# LiPo-USB-Charger-v10.net
KiCad netlist of a schematic drawn in EAGLE
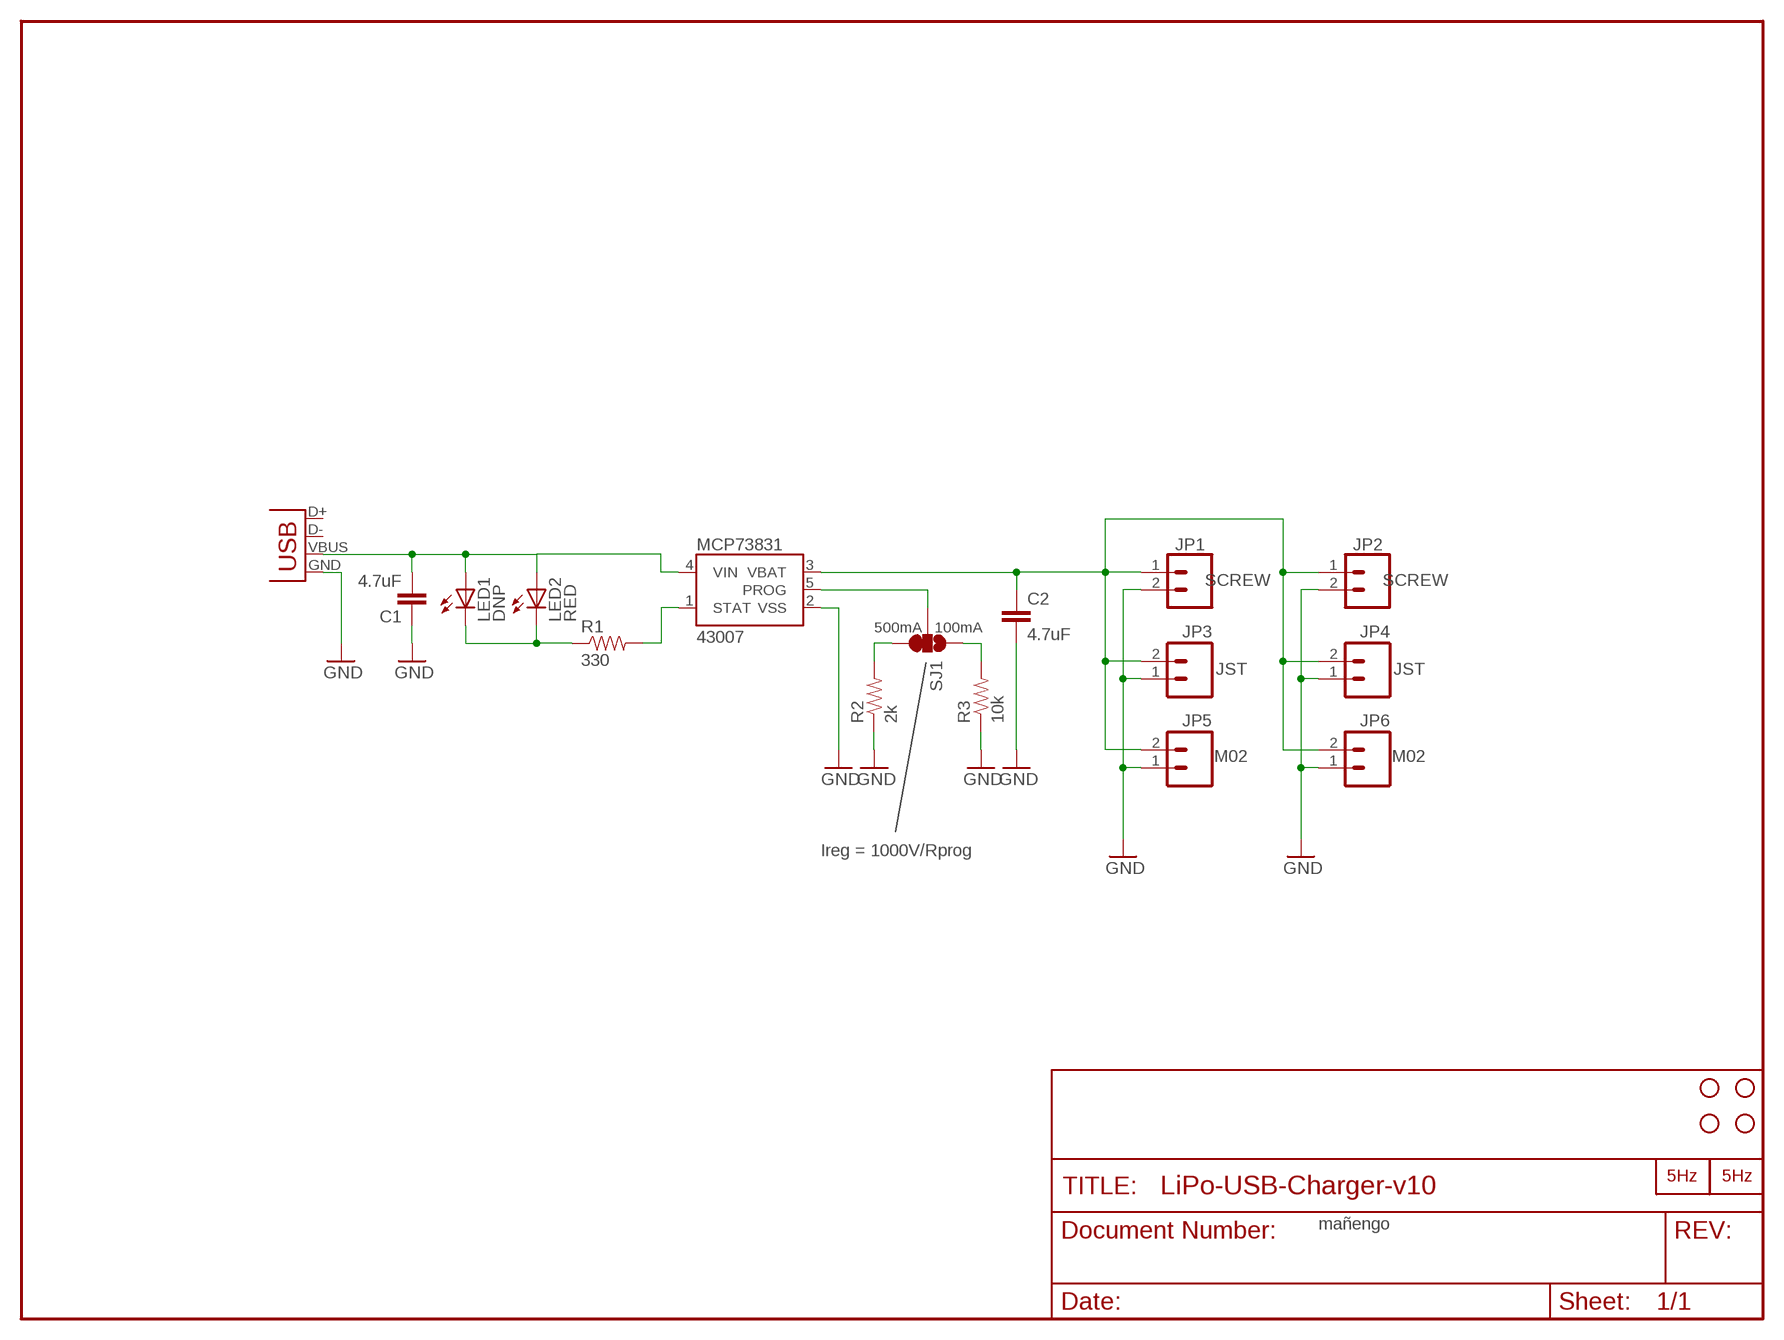
[diagram p0: schematic, sheet 1]

(export (version "E")
  (design (tool "Eeschema 10.0.6"))
  (components
    (comp (ref "C1")
      (value "4.7uF")
      (footprint "eagle-import:0402-CAP")
      (libsource (lib "eagle-import") (part "CAP0402-CAP"))
    )
    (comp (ref "C2")
      (value "4.7uF")
      (footprint "eagle-import:0402-CAP")
      (libsource (lib "eagle-import") (part "CAP0402-CAP"))
    )
    (comp (ref "JP1")
      (value "SCREW")
      (footprint "eagle-import:SCREWTERMINAL-3.5MM-2-NS")
      (libsource (lib "eagle-import") (part "M023.5MM-NO_SILK"))
    )
    (comp (ref "JP2")
      (value "SCREW")
      (footprint "eagle-import:SCREWTERMINAL-3.5MM-2-NS")
      (libsource (lib "eagle-import") (part "M023.5MM-NO_SILK"))
    )
    (comp (ref "JP3")
      (value "JST")
      (footprint "eagle-import:JST-2-PTH")
      (libsource (lib "eagle-import") (part "M02JST-PTH-2"))
    )
    (comp (ref "JP4")
      (value "JST")
      (footprint "eagle-import:JST-2-PTH")
      (libsource (lib "eagle-import") (part "M02JST-PTH-2"))
    )
    (comp (ref "JP5")
      (value "M02")
      (footprint "eagle-import:1X02")
      (libsource (lib "eagle-import") (part "M02PTH"))
    )
    (comp (ref "JP6")
      (value "M02")
      (footprint "eagle-import:1X02")
      (libsource (lib "eagle-import") (part "M02PTH"))
    )
    (comp (ref "JP7")
      (value "STAND-OFF")
      (footprint "eagle-import:STAND-OFF")
      (libsource (lib "eagle-import") (part "STAND-OFF"))
    )
    (comp (ref "JP8")
      (value "STAND-OFF")
      (footprint "eagle-import:STAND-OFF")
      (libsource (lib "eagle-import") (part "STAND-OFF"))
    )
    (comp (ref "JP9")
      (value "STAND-OFF")
      (footprint "eagle-import:STAND-OFF")
      (libsource (lib "eagle-import") (part "STAND-OFF"))
    )
    (comp (ref "JP10")
      (value "STAND-OFF")
      (footprint "eagle-import:STAND-OFF")
      (libsource (lib "eagle-import") (part "STAND-OFF"))
    )
    (comp (ref "LED1")
      (value "DNP")
      (footprint "eagle-import:LED3MM")
      (libsource (lib "eagle-import") (part "LED3MM"))
    )
    (comp (ref "LED2")
      (value "RED")
      (footprint "eagle-import:LED-0603")
      (libsource (lib "eagle-import") (part "LED0603"))
    )
    (comp (ref "MCP73831")
      (value "43007")
      (footprint "eagle-import:SOT23-5")
      (libsource (lib "eagle-import") (part "MCP73831"))
    )
    (comp (ref "R1")
      (value "330")
      (footprint "eagle-import:0402-RES")
      (libsource (lib "eagle-import") (part "RESISTOR0402-RES"))
    )
    (comp (ref "R2")
      (value "2k")
      (footprint "eagle-import:0402-RES")
      (libsource (lib "eagle-import") (part "RESISTOR0402-RES"))
    )
    (comp (ref "R3")
      (value "10k")
      (footprint "eagle-import:0402-RES")
      (libsource (lib "eagle-import") (part "RESISTOR0402-RES"))
    )
    (comp (ref "SJ1")
      (value "SOLDERJUMPER_2WAYS")
      (footprint "eagle-import:SJ_3")
      (libsource (lib "eagle-import") (part "SOLDERJUMPER_2WAYS"))
    )
    (comp (ref "U$1")
      (value "LOGO_COPPER10MM")
      (footprint "eagle-import:LOGO_COP_10MM")
      (libsource (lib "eagle-import") (part "LOGO_COPPER10MM"))
    )
    (comp (ref "U$2")
      (value "LOGO2_SILK5MM")
      (footprint "eagle-import:LOGO2_5MM")
      (libsource (lib "eagle-import") (part "LOGO2_SILK5MM"))
    )
    (comp (ref "X1")
      (value "USBSMD")
      (footprint "eagle-import:USB-MINIB")
      (libsource (lib "eagle-import") (part "USBSMD"))
    )
  )
  (nets
    (net (code "1") (name "GND") (class "Default")
      (node (ref "C1") (pin "1") (pinfunction "1_1") (pintype "passive"))
      (node (ref "C2") (pin "2") (pinfunction "2_2") (pintype "passive"))
      (node (ref "JP1") (pin "2") (pinfunction "2_2") (pintype "passive"))
      (node (ref "JP2") (pin "2") (pinfunction "2_2") (pintype "passive"))
      (node (ref "JP3") (pin "1") (pinfunction "1_1") (pintype "passive"))
      (node (ref "JP4") (pin "1") (pinfunction "1_1") (pintype "passive"))
      (node (ref "JP5") (pin "1") (pinfunction "1_1") (pintype "passive"))
      (node (ref "JP6") (pin "1") (pinfunction "1_1") (pintype "passive"))
      (node (ref "MCP73831") (pin "2") (pinfunction "VSS_2") (pintype "power_in"))
      (node (ref "R2") (pin "1") (pinfunction "1_1") (pintype "passive"))
      (node (ref "R3") (pin "1") (pinfunction "1_1") (pintype "passive"))
      (node (ref "X1") (pin "GND") (pinfunction "GND_GND") (pintype "bidirectional"))
    )
    (net (code "2") (name "Net-(LED1-C)") (class "Default")
      (node (ref "LED1") (pin "K") (pinfunction "C_K") (pintype "passive"))
      (node (ref "LED2") (pin "C") (pinfunction "C_C") (pintype "passive"))
      (node (ref "R1") (pin "1") (pinfunction "1_1") (pintype "passive"))
    )
    (net (code "3") (name "Net-(MCP73831-PROG)") (class "Default")
      (node (ref "MCP73831") (pin "5") (pinfunction "PROG_5") (pintype "input"))
      (node (ref "SJ1") (pin "2") (pinfunction "2_2") (pintype "passive"))
    )
    (net (code "4") (name "Net-(MCP73831-STAT)") (class "Default")
      (node (ref "MCP73831") (pin "1") (pinfunction "STAT_1") (pintype "output"))
      (node (ref "R1") (pin "2") (pinfunction "2_2") (pintype "passive"))
    )
    (net (code "5") (name "Net-(MCP73831-VBAT)") (class "Default")
      (node (ref "C2") (pin "1") (pinfunction "1_1") (pintype "passive"))
      (node (ref "JP1") (pin "1") (pinfunction "1_1") (pintype "passive"))
      (node (ref "JP2") (pin "1") (pinfunction "1_1") (pintype "passive"))
      (node (ref "JP3") (pin "2") (pinfunction "2_2") (pintype "passive"))
      (node (ref "JP4") (pin "2") (pinfunction "2_2") (pintype "passive"))
      (node (ref "JP5") (pin "2") (pinfunction "2_2") (pintype "passive"))
      (node (ref "JP6") (pin "2") (pinfunction "2_2") (pintype "passive"))
      (node (ref "MCP73831") (pin "3") (pinfunction "VBAT_3") (pintype "power_in"))
    )
    (net (code "6") (name "Net-(MCP73831-VIN)") (class "Default")
      (node (ref "C1") (pin "2") (pinfunction "2_2") (pintype "passive"))
      (node (ref "LED1") (pin "A") (pinfunction "A_A") (pintype "passive"))
      (node (ref "LED2") (pin "A") (pinfunction "A_A") (pintype "passive"))
      (node (ref "MCP73831") (pin "4") (pinfunction "VIN_4") (pintype "power_in"))
      (node (ref "X1") (pin "VBUS") (pinfunction "VBUS_VBUS") (pintype "bidirectional"))
    )
    (net (code "7") (name "Net-(R2-Pad2)") (class "Default")
      (node (ref "R2") (pin "2") (pinfunction "2_2") (pintype "passive"))
      (node (ref "SJ1") (pin "3") (pinfunction "3_3") (pintype "passive"))
    )
    (net (code "8") (name "Net-(R3-Pad2)") (class "Default")
      (node (ref "R3") (pin "2") (pinfunction "2_2") (pintype "passive"))
      (node (ref "SJ1") (pin "1") (pinfunction "1_1") (pintype "passive"))
    )
    (net (code "9") (name "unconnected-(X1-PadD+)") (class "Default")
      (node (ref "X1") (pin "D+") (pinfunction "D+_D+") (pintype "bidirectional"))
    )
    (net (code "10") (name "unconnected-(X1-PadD-)") (class "Default")
      (node (ref "X1") (pin "D-") (pinfunction "D-_D-") (pintype "bidirectional"))
    )
  )
)
